# Phoreo.net
KiCad netlist of a schematic drawn in EAGLE
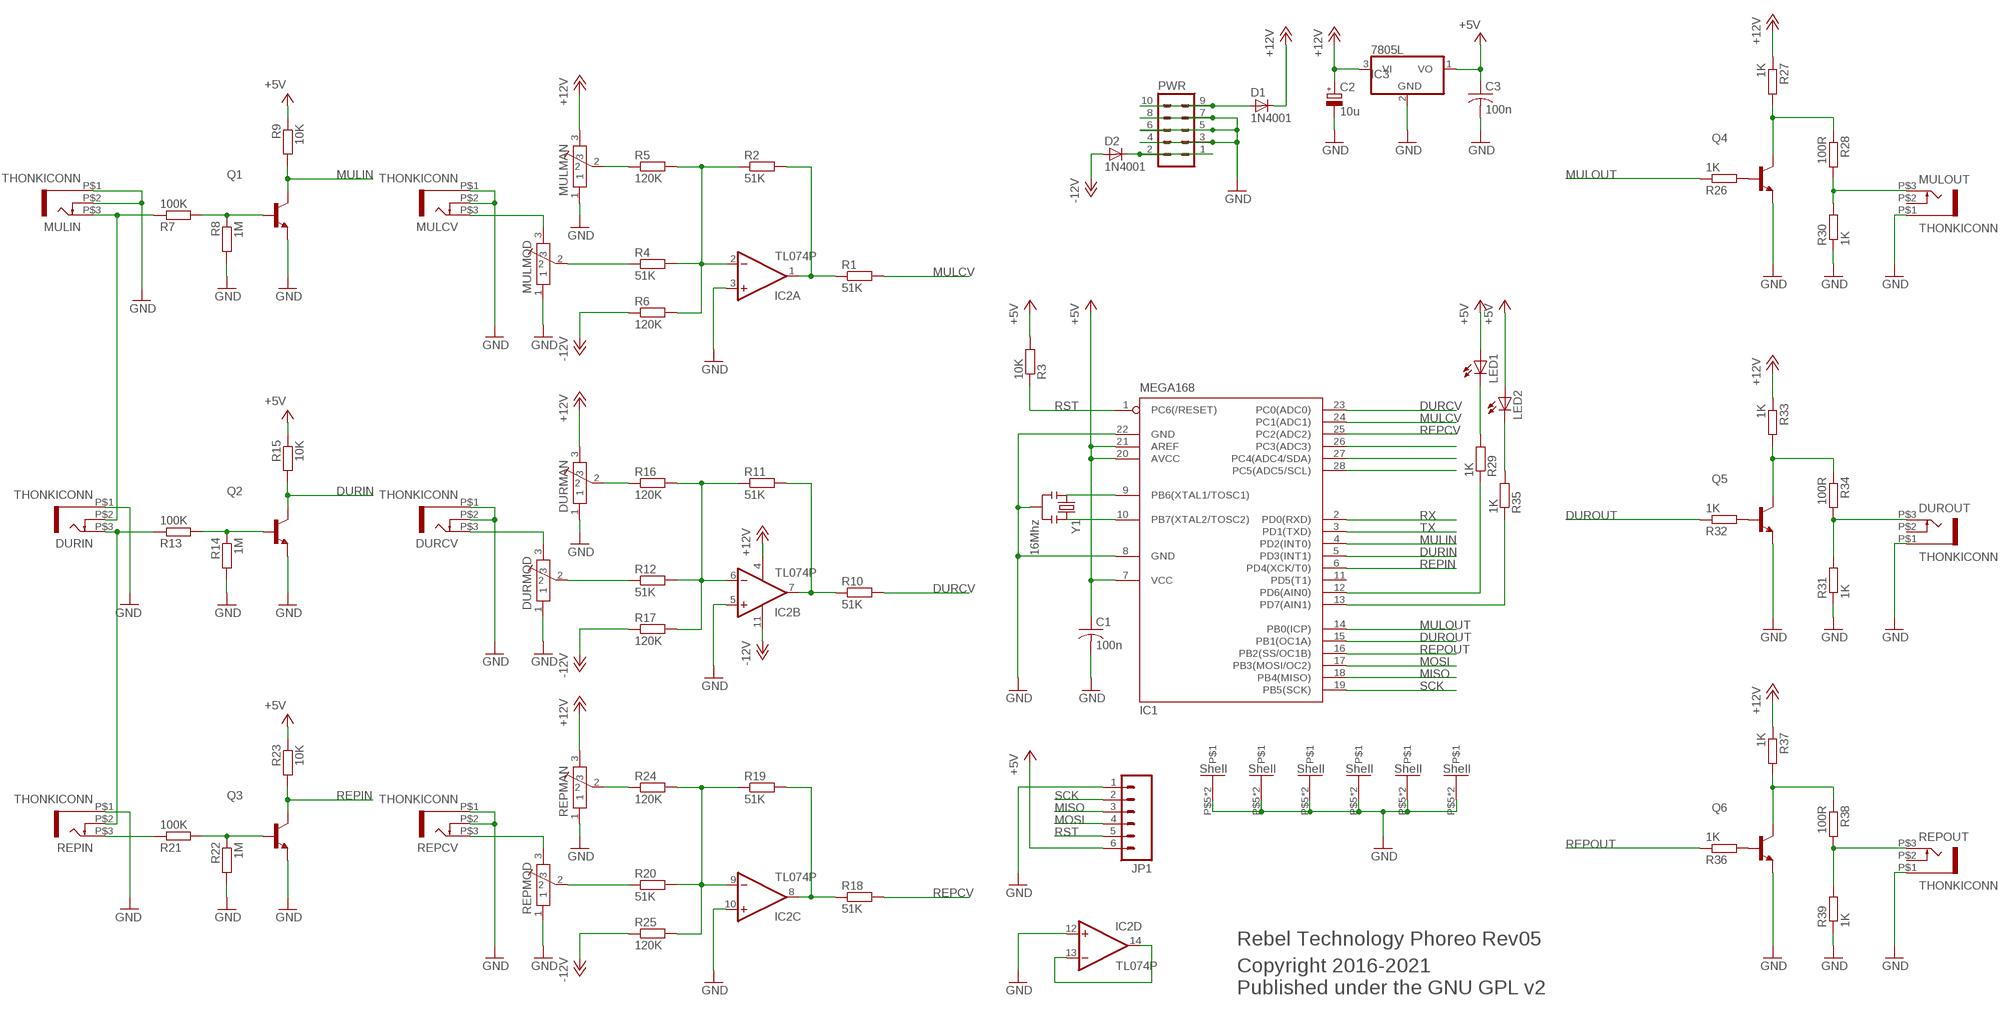
[diagram p0: schematic, sheet 1]

(export (version "E")
  (design (tool "Eeschema 10.0.6"))
  (components
    (comp (ref "C1")
      (value "100n")
      (footprint "eagle-import:C050-024X044")
      (libsource (lib "eagle-import") (part "C-US050-024X044"))
    )
    (comp (ref "C2")
      (value "10u")
      (footprint "eagle-import:E5-6")
      (libsource (lib "eagle-import") (part "CPOL-EUE5-6"))
    )
    (comp (ref "C3")
      (value "100n")
      (footprint "eagle-import:C050-024X044")
      (libsource (lib "eagle-import") (part "C-US050-024X044"))
    )
    (comp (ref "D1")
      (value "1N4001")
      (footprint "eagle-import:DIODE-1N4001")
      (libsource (lib "eagle-import") (part "DIODE1N4001"))
    )
    (comp (ref "D2")
      (value "1N4001")
      (footprint "eagle-import:DIODE-1N4001")
      (libsource (lib "eagle-import") (part "DIODE1N4001"))
    )
    (comp (ref "DURCV")
      (value "THONKICONN")
      (footprint "eagle-import:THONKICONN")
      (libsource (lib "eagle-import") (part "THONKICONN"))
    )
    (comp (ref "DURIN")
      (value "THONKICONN")
      (footprint "eagle-import:THONKICONN")
      (libsource (lib "eagle-import") (part "THONKICONN"))
    )
    (comp (ref "DURMAN")
      (value "POT-ALPS-RK09L1140")
      (footprint "eagle-import:POT-ALPS-RK09L1140")
      (libsource (lib "eagle-import") (part "POT-ALPS-RK09L1140"))
    )
    (comp (ref "DURMOD")
      (value "POT-ALPS-RK09L1140")
      (footprint "eagle-import:POT-ALPS-RK09L1140")
      (libsource (lib "eagle-import") (part "POT-ALPS-RK09L1140"))
    )
    (comp (ref "DUROUT")
      (value "THONKICONN")
      (footprint "eagle-import:THONKICONN")
      (libsource (lib "eagle-import") (part "THONKICONN"))
    )
    (comp (ref "IC1")
      (value "MEGA168")
      (footprint "eagle-import:DIL28-3")
      (libsource (lib "eagle-import") (part "MEGA8-P"))
    )
    (comp (ref "IC2")
      (value "TL074P")
      (footprint "eagle-import:DIL14")
      (libsource (lib "eagle-import") (part "TL074P"))
    )
    (comp (ref "IC3")
      (value "7805L")
      (footprint "eagle-import:TO92")
      (libsource (lib "eagle-import") (part "78L05"))
    )
    (comp (ref "JP1")
      (value "M06SIP")
      (footprint "eagle-import:1X06")
      (libsource (lib "eagle-import") (part "M06SIP"))
    )
    (comp (ref "LED1")
      (value "LED3MM")
      (footprint "eagle-import:LED3MM")
      (libsource (lib "eagle-import") (part "LED3MM"))
    )
    (comp (ref "LED2")
      (value "LED3MM")
      (footprint "eagle-import:LED3MM")
      (libsource (lib "eagle-import") (part "LED3MM"))
    )
    (comp (ref "MULCV")
      (value "THONKICONN")
      (footprint "eagle-import:THONKICONN")
      (libsource (lib "eagle-import") (part "THONKICONN"))
    )
    (comp (ref "MULIN")
      (value "THONKICONN")
      (footprint "eagle-import:THONKICONN")
      (libsource (lib "eagle-import") (part "THONKICONN"))
    )
    (comp (ref "MULMAN")
      (value "POT-ALPS-RK09L1140")
      (footprint "eagle-import:POT-ALPS-RK09L1140")
      (libsource (lib "eagle-import") (part "POT-ALPS-RK09L1140"))
    )
    (comp (ref "MULMOD")
      (value "POT-ALPS-RK09L1140")
      (footprint "eagle-import:POT-ALPS-RK09L1140")
      (libsource (lib "eagle-import") (part "POT-ALPS-RK09L1140"))
    )
    (comp (ref "MULOUT")
      (value "THONKICONN")
      (footprint "eagle-import:THONKICONN")
      (libsource (lib "eagle-import") (part "THONKICONN"))
    )
    (comp (ref "PWR")
      (value "MA05-2")
      (footprint "eagle-import:MA05-2")
      (libsource (lib "eagle-import") (part "MA05-2"))
    )
    (comp (ref "Q1")
      (value "2N3904-NPN-TO92-EBC")
      (footprint "eagle-import:TO92-EBC")
      (libsource (lib "eagle-import") (part "-NPN-TO92-EBC2N3904"))
    )
    (comp (ref "Q2")
      (value "2N3904-NPN-TO92-EBC")
      (footprint "eagle-import:TO92-EBC")
      (libsource (lib "eagle-import") (part "-NPN-TO92-EBC2N3904"))
    )
    (comp (ref "Q3")
      (value "2N3904-NPN-TO92-EBC")
      (footprint "eagle-import:TO92-EBC")
      (libsource (lib "eagle-import") (part "-NPN-TO92-EBC2N3904"))
    )
    (comp (ref "Q4")
      (value "2N3904-NPN-TO92-EBC")
      (footprint "eagle-import:TO92-EBC")
      (libsource (lib "eagle-import") (part "-NPN-TO92-EBC2N3904"))
    )
    (comp (ref "Q5")
      (value "2N3904-NPN-TO92-EBC")
      (footprint "eagle-import:TO92-EBC")
      (libsource (lib "eagle-import") (part "-NPN-TO92-EBC2N3904"))
    )
    (comp (ref "Q6")
      (value "2N3904-NPN-TO92-EBC")
      (footprint "eagle-import:TO92-EBC")
      (libsource (lib "eagle-import") (part "-NPN-TO92-EBC2N3904"))
    )
    (comp (ref "R1")
      (value "51K")
      (footprint "eagle-import:0204_7")
      (libsource (lib "eagle-import") (part "R-EU_0204/7"))
    )
    (comp (ref "R2")
      (value "51K")
      (footprint "eagle-import:0204_7")
      (libsource (lib "eagle-import") (part "R-EU_0204/7"))
    )
    (comp (ref "R3")
      (value "10K")
      (footprint "eagle-import:0204_7")
      (libsource (lib "eagle-import") (part "R-EU_0204/7"))
    )
    (comp (ref "R4")
      (value "51K")
      (footprint "eagle-import:0204_7")
      (libsource (lib "eagle-import") (part "R-EU_0204/7"))
    )
    (comp (ref "R5")
      (value "120K")
      (footprint "eagle-import:0204_7")
      (libsource (lib "eagle-import") (part "R-EU_0204/7"))
    )
    (comp (ref "R6")
      (value "120K")
      (footprint "eagle-import:0204_7")
      (libsource (lib "eagle-import") (part "R-EU_0204/7"))
    )
    (comp (ref "R7")
      (value "100K")
      (footprint "eagle-import:0204_7")
      (libsource (lib "eagle-import") (part "R-EU_0204/7"))
    )
    (comp (ref "R8")
      (value "1M")
      (footprint "eagle-import:0204_7")
      (libsource (lib "eagle-import") (part "R-EU_0204/7"))
    )
    (comp (ref "R9")
      (value "10K")
      (footprint "eagle-import:0204_7")
      (libsource (lib "eagle-import") (part "R-EU_0204/7"))
    )
    (comp (ref "R10")
      (value "51K")
      (footprint "eagle-import:0204_7")
      (libsource (lib "eagle-import") (part "R-EU_0204/7"))
    )
    (comp (ref "R11")
      (value "51K")
      (footprint "eagle-import:0204_7")
      (libsource (lib "eagle-import") (part "R-EU_0204/7"))
    )
    (comp (ref "R12")
      (value "51K")
      (footprint "eagle-import:0204_7")
      (libsource (lib "eagle-import") (part "R-EU_0204/7"))
    )
    (comp (ref "R13")
      (value "100K")
      (footprint "eagle-import:0204_7")
      (libsource (lib "eagle-import") (part "R-EU_0204/7"))
    )
    (comp (ref "R14")
      (value "1M")
      (footprint "eagle-import:0204_7")
      (libsource (lib "eagle-import") (part "R-EU_0204/7"))
    )
    (comp (ref "R15")
      (value "10K")
      (footprint "eagle-import:0204_7")
      (libsource (lib "eagle-import") (part "R-EU_0204/7"))
    )
    (comp (ref "R16")
      (value "120K")
      (footprint "eagle-import:0204_7")
      (libsource (lib "eagle-import") (part "R-EU_0204/7"))
    )
    (comp (ref "R17")
      (value "120K")
      (footprint "eagle-import:0204_7")
      (libsource (lib "eagle-import") (part "R-EU_0204/7"))
    )
    (comp (ref "R18")
      (value "51K")
      (footprint "eagle-import:0204_7")
      (libsource (lib "eagle-import") (part "R-EU_0204/7"))
    )
    (comp (ref "R19")
      (value "51K")
      (footprint "eagle-import:0204_7")
      (libsource (lib "eagle-import") (part "R-EU_0204/7"))
    )
    (comp (ref "R20")
      (value "51K")
      (footprint "eagle-import:0204_7")
      (libsource (lib "eagle-import") (part "R-EU_0204/7"))
    )
    (comp (ref "R21")
      (value "100K")
      (footprint "eagle-import:0204_7")
      (libsource (lib "eagle-import") (part "R-EU_0204/7"))
    )
    (comp (ref "R22")
      (value "1M")
      (footprint "eagle-import:0204_7")
      (libsource (lib "eagle-import") (part "R-EU_0204/7"))
    )
    (comp (ref "R23")
      (value "10K")
      (footprint "eagle-import:0204_7")
      (libsource (lib "eagle-import") (part "R-EU_0204/7"))
    )
    (comp (ref "R24")
      (value "120K")
      (footprint "eagle-import:0204_7")
      (libsource (lib "eagle-import") (part "R-EU_0204/7"))
    )
    (comp (ref "R25")
      (value "120K")
      (footprint "eagle-import:0204_7")
      (libsource (lib "eagle-import") (part "R-EU_0204/7"))
    )
    (comp (ref "R26")
      (value "1K")
      (footprint "eagle-import:0204_7")
      (libsource (lib "eagle-import") (part "R-EU_0204/7"))
    )
    (comp (ref "R27")
      (value "1K")
      (footprint "eagle-import:0204_7")
      (libsource (lib "eagle-import") (part "R-EU_0204/7"))
    )
    (comp (ref "R28")
      (value "100R")
      (footprint "eagle-import:0204_7")
      (libsource (lib "eagle-import") (part "R-EU_0204/7"))
    )
    (comp (ref "R29")
      (value "1K")
      (footprint "eagle-import:0204_7")
      (libsource (lib "eagle-import") (part "R-EU_0204/7"))
    )
    (comp (ref "R30")
      (value "1K")
      (footprint "eagle-import:0204_7")
      (libsource (lib "eagle-import") (part "R-EU_0204/7"))
    )
    (comp (ref "R31")
      (value "1K")
      (footprint "eagle-import:0204_7")
      (libsource (lib "eagle-import") (part "R-EU_0204/7"))
    )
    (comp (ref "R32")
      (value "1K")
      (footprint "eagle-import:0204_7")
      (libsource (lib "eagle-import") (part "R-EU_0204/7"))
    )
    (comp (ref "R33")
      (value "1K")
      (footprint "eagle-import:0204_7")
      (libsource (lib "eagle-import") (part "R-EU_0204/7"))
    )
    (comp (ref "R34")
      (value "100R")
      (footprint "eagle-import:0204_7")
      (libsource (lib "eagle-import") (part "R-EU_0204/7"))
    )
    (comp (ref "R35")
      (value "1K")
      (footprint "eagle-import:0204_7")
      (libsource (lib "eagle-import") (part "R-EU_0204/7"))
    )
    (comp (ref "R36")
      (value "1K")
      (footprint "eagle-import:0204_7")
      (libsource (lib "eagle-import") (part "R-EU_0204/7"))
    )
    (comp (ref "R37")
      (value "1K")
      (footprint "eagle-import:0204_7")
      (libsource (lib "eagle-import") (part "R-EU_0204/7"))
    )
    (comp (ref "R38")
      (value "100R")
      (footprint "eagle-import:0204_7")
      (libsource (lib "eagle-import") (part "R-EU_0204/7"))
    )
    (comp (ref "R39")
      (value "1K")
      (footprint "eagle-import:0204_7")
      (libsource (lib "eagle-import") (part "R-EU_0204/7"))
    )
    (comp (ref "REPCV")
      (value "THONKICONN")
      (footprint "eagle-import:THONKICONN")
      (libsource (lib "eagle-import") (part "THONKICONN"))
    )
    (comp (ref "REPIN")
      (value "THONKICONN")
      (footprint "eagle-import:THONKICONN")
      (libsource (lib "eagle-import") (part "THONKICONN"))
    )
    (comp (ref "REPMAN")
      (value "POT-ALPS-RK09L1140")
      (footprint "eagle-import:POT-ALPS-RK09L1140")
      (libsource (lib "eagle-import") (part "POT-ALPS-RK09L1140"))
    )
    (comp (ref "REPMOD")
      (value "POT-ALPS-RK09L1140")
      (footprint "eagle-import:POT-ALPS-RK09L1140")
      (libsource (lib "eagle-import") (part "POT-ALPS-RK09L1140"))
    )
    (comp (ref "REPOUT")
      (value "THONKICONN")
      (footprint "eagle-import:THONKICONN")
      (libsource (lib "eagle-import") (part "THONKICONN"))
    )
    (comp (ref "Y1")
      (value "16Mhz")
      (footprint "eagle-import:RESONATOR-PTH")
      (libsource (lib "eagle-import") (part "RESONATORPTH"))
    )
  )
  (nets
    (net (code "1") (name "+5V") (class "Default")
      (node (ref "C1") (pin "1") (pinfunction "1_1") (pintype "passive"))
      (node (ref "C3") (pin "1") (pinfunction "1_1") (pintype "passive"))
      (node (ref "IC1") (pin "20") (pinfunction "AVCC_20") (pintype "power_in"))
      (node (ref "IC1") (pin "21") (pinfunction "AREF_21") (pintype "passive"))
      (node (ref "IC1") (pin "7") (pinfunction "VCC_7") (pintype "power_in"))
      (node (ref "IC3") (pin "1") (pinfunction "VO_1") (pintype "passive"))
      (node (ref "JP1") (pin "6") (pinfunction "6_6") (pintype "passive"))
      (node (ref "LED1") (pin "A") (pinfunction "A_A") (pintype "passive"))
      (node (ref "LED2") (pin "A") (pinfunction "A_A") (pintype "passive"))
      (node (ref "R15") (pin "1") (pinfunction "1_1") (pintype "passive"))
      (node (ref "R23") (pin "1") (pinfunction "1_1") (pintype "passive"))
      (node (ref "R3") (pin "2") (pinfunction "2_2") (pintype "passive"))
      (node (ref "R9") (pin "1") (pinfunction "1_1") (pintype "passive"))
    )
    (net (code "2") (name "+12V") (class "Default")
      (node (ref "C2") (pin "+") (pinfunction "+_+") (pintype "passive"))
      (node (ref "D1") (pin "C") (pinfunction "C_C") (pintype "passive"))
      (node (ref "DURMAN") (pin "3") (pinfunction "3_3") (pintype "bidirectional"))
      (node (ref "IC2") (pin "4") (pinfunction "V+_4") (pintype "power_in"))
      (node (ref "IC3") (pin "3") (pinfunction "VI_3") (pintype "input"))
      (node (ref "MULMAN") (pin "3") (pinfunction "3_3") (pintype "bidirectional"))
      (node (ref "R27") (pin "1") (pinfunction "1_1") (pintype "passive"))
      (node (ref "R33") (pin "1") (pinfunction "1_1") (pintype "passive"))
      (node (ref "R37") (pin "1") (pinfunction "1_1") (pintype "passive"))
      (node (ref "REPMAN") (pin "3") (pinfunction "3_3") (pintype "bidirectional"))
    )
    (net (code "3") (name "-12V") (class "Default")
      (node (ref "D2") (pin "A") (pinfunction "A_A") (pintype "passive"))
      (node (ref "IC2") (pin "11") (pinfunction "V-_11") (pintype "power_in"))
      (node (ref "R17") (pin "1") (pinfunction "1_1") (pintype "passive"))
      (node (ref "R25") (pin "1") (pinfunction "1_1") (pintype "passive"))
      (node (ref "R6") (pin "1") (pinfunction "1_1") (pintype "passive"))
    )
    (net (code "4") (name "/DURCV") (class "Default")
      (node (ref "IC1") (pin "23") (pinfunction "PC0(ADC0)_23") (pintype "bidirectional"))
      (node (ref "R10") (pin "2") (pinfunction "2_2") (pintype "passive"))
    )
    (net (code "5") (name "/DURIN") (class "Default")
      (node (ref "IC1") (pin "5") (pinfunction "PD3(INT1)_5") (pintype "bidirectional"))
      (node (ref "Q2") (pin "C") (pinfunction "C_C") (pintype "passive"))
      (node (ref "R15") (pin "2") (pinfunction "2_2") (pintype "passive"))
    )
    (net (code "6") (name "/DUROUT") (class "Default")
      (node (ref "IC1") (pin "15") (pinfunction "PB1(OC1A)_15") (pintype "bidirectional"))
      (node (ref "R32") (pin "1") (pinfunction "1_1") (pintype "passive"))
    )
    (net (code "7") (name "/MISO") (class "Default")
      (node (ref "IC1") (pin "18") (pinfunction "PB4(MISO)_18") (pintype "bidirectional"))
      (node (ref "JP1") (pin "3") (pinfunction "3_3") (pintype "passive"))
    )
    (net (code "8") (name "/MOSI") (class "Default")
      (node (ref "IC1") (pin "17") (pinfunction "PB3(MOSI/OC2)_17") (pintype "bidirectional"))
      (node (ref "JP1") (pin "4") (pinfunction "4_4") (pintype "passive"))
    )
    (net (code "9") (name "/MULCV") (class "Default")
      (node (ref "IC1") (pin "24") (pinfunction "PC1(ADC1)_24") (pintype "bidirectional"))
      (node (ref "R1") (pin "2") (pinfunction "2_2") (pintype "passive"))
    )
    (net (code "10") (name "/MULIN") (class "Default")
      (node (ref "IC1") (pin "4") (pinfunction "PD2(INT0)_4") (pintype "bidirectional"))
      (node (ref "Q1") (pin "C") (pinfunction "C_C") (pintype "passive"))
      (node (ref "R9") (pin "2") (pinfunction "2_2") (pintype "passive"))
    )
    (net (code "11") (name "/MULOUT") (class "Default")
      (node (ref "IC1") (pin "14") (pinfunction "PB0(ICP)_14") (pintype "bidirectional"))
      (node (ref "R26") (pin "1") (pinfunction "1_1") (pintype "passive"))
    )
    (net (code "12") (name "/REPCV") (class "Default")
      (node (ref "IC1") (pin "25") (pinfunction "PC2(ADC2)_25") (pintype "bidirectional"))
      (node (ref "R18") (pin "2") (pinfunction "2_2") (pintype "passive"))
    )
    (net (code "13") (name "/REPIN") (class "Default")
      (node (ref "IC1") (pin "6") (pinfunction "PD4(XCK/T0)_6") (pintype "bidirectional"))
      (node (ref "Q3") (pin "C") (pinfunction "C_C") (pintype "passive"))
      (node (ref "R23") (pin "2") (pinfunction "2_2") (pintype "passive"))
    )
    (net (code "14") (name "/REPOUT") (class "Default")
      (node (ref "IC1") (pin "16") (pinfunction "PB2(SS/OC1B)_16") (pintype "bidirectional"))
      (node (ref "R36") (pin "1") (pinfunction "1_1") (pintype "passive"))
    )
    (net (code "15") (name "/RST") (class "Default")
      (node (ref "IC1") (pin "1") (pinfunction "PC6(/RESET)_1") (pintype "bidirectional"))
      (node (ref "JP1") (pin "5") (pinfunction "5_5") (pintype "passive"))
      (node (ref "R3") (pin "1") (pinfunction "1_1") (pintype "passive"))
    )
    (net (code "16") (name "/RX") (class "Default")
      (node (ref "IC1") (pin "2") (pinfunction "PD0(RXD)_2") (pintype "bidirectional"))
    )
    (net (code "17") (name "/SCK") (class "Default")
      (node (ref "IC1") (pin "19") (pinfunction "PB5(SCK)_19") (pintype "bidirectional"))
      (node (ref "JP1") (pin "2") (pinfunction "2_2") (pintype "passive"))
    )
    (net (code "18") (name "/TX") (class "Default")
      (node (ref "IC1") (pin "3") (pinfunction "PD1(TXD)_3") (pintype "bidirectional"))
    )
    (net (code "19") (name "GND") (class "Default")
      (node (ref "C1") (pin "2") (pinfunction "2_2") (pintype "passive"))
      (node (ref "C2") (pin "-") (pinfunction "-_-") (pintype "passive"))
      (node (ref "C3") (pin "2") (pinfunction "2_2") (pintype "passive"))
      (node (ref "DURCV") (pin "P$1") (pinfunction "5_P$1") (pintype "passive"))
      (node (ref "DURCV") (pin "P$2") (pinfunction "4_P$2") (pintype "passive"))
      (node (ref "DURIN") (pin "P$1") (pinfunction "5_P$1") (pintype "passive"))
      (node (ref "DURMAN") (pin "1") (pinfunction "1_1") (pintype "bidirectional"))
      (node (ref "DURMAN") (pin "P$5") (pinfunction "P$1_P$5") (pintype "bidirectional"))
      (node (ref "DURMAN") (pin "P$6") (pinfunction "P$1_P$6") (pintype "bidirectional"))
      (node (ref "DURMOD") (pin "1") (pinfunction "1_1") (pintype "bidirectional"))
      (node (ref "DURMOD") (pin "P$5") (pinfunction "P$1_P$5") (pintype "bidirectional"))
      (node (ref "DURMOD") (pin "P$6") (pinfunction "P$1_P$6") (pintype "bidirectional"))
      (node (ref "DUROUT") (pin "P$1") (pinfunction "5_P$1") (pintype "passive"))
      (node (ref "IC1") (pin "22") (pinfunction "GND_22") (pintype "power_in"))
      (node (ref "IC1") (pin "8") (pinfunction "GND_8") (pintype "power_in"))
      (node (ref "IC2") (pin "10") (pinfunction "+IN_10") (pintype "input"))
      (node (ref "IC2") (pin "12") (pinfunction "+IN_12") (pintype "input"))
      (node (ref "IC2") (pin "3") (pinfunction "+IN_3") (pintype "input"))
      (node (ref "IC2") (pin "5") (pinfunction "+IN_5") (pintype "input"))
      (node (ref "IC3") (pin "2") (pinfunction "GND_2") (pintype "passive"))
      (node (ref "JP1") (pin "1") (pinfunction "1_1") (pintype "passive"))
      (node (ref "MULCV") (pin "P$1") (pinfunction "5_P$1") (pintype "passive"))
      (node (ref "MULCV") (pin "P$2") (pinfunction "4_P$2") (pintype "passive"))
      (node (ref "MULIN") (pin "P$1") (pinfunction "5_P$1") (pintype "passive"))
      (node (ref "MULIN") (pin "P$2") (pinfunction "4_P$2") (pintype "passive"))
      (node (ref "MULMAN") (pin "1") (pinfunction "1_1") (pintype "bidirectional"))
      (node (ref "MULMAN") (pin "P$5") (pinfunction "P$1_P$5") (pintype "bidirectional"))
      (node (ref "MULMAN") (pin "P$6") (pinfunction "P$1_P$6") (pintype "bidirectional"))
      (node (ref "MULMOD") (pin "1") (pinfunction "1_1") (pintype "bidirectional"))
      (node (ref "MULMOD") (pin "P$5") (pinfunction "P$1_P$5") (pintype "bidirectional"))
      (node (ref "MULMOD") (pin "P$6") (pinfunction "P$1_P$6") (pintype "bidirectional"))
      (node (ref "MULOUT") (pin "P$1") (pinfunction "5_P$1") (pintype "passive"))
      (node (ref "PWR") (pin "3") (pinfunction "3_3") (pintype "passive"))
      (node (ref "PWR") (pin "4") (pinfunction "4_4") (pintype "passive"))
      (node (ref "PWR") (pin "5") (pinfunction "5_5") (pintype "passive"))
      (node (ref "PWR") (pin "6") (pinfunction "6_6") (pintype "passive"))
      (node (ref "PWR") (pin "7") (pinfunction "7_7") (pintype "passive"))
      (node (ref "PWR") (pin "8") (pinfunction "8_8") (pintype "passive"))
      (node (ref "Q1") (pin "E") (pinfunction "E_E") (pintype "passive"))
      (node (ref "Q2") (pin "E") (pinfunction "E_E") (pintype "passive"))
      (node (ref "Q3") (pin "E") (pinfunction "E_E") (pintype "passive"))
      (node (ref "Q4") (pin "E") (pinfunction "E_E") (pintype "passive"))
      (node (ref "Q5") (pin "E") (pinfunction "E_E") (pintype "passive"))
      (node (ref "Q6") (pin "E") (pinfunction "E_E") (pintype "passive"))
      (node (ref "R14") (pin "2") (pinfunction "2_2") (pintype "passive"))
      (node (ref "R22") (pin "2") (pinfunction "2_2") (pintype "passive"))
      (node (ref "R30") (pin "1") (pinfunction "1_1") (pintype "passive"))
      (node (ref "R31") (pin "1") (pinfunction "1_1") (pintype "passive"))
      (node (ref "R39") (pin "1") (pinfunction "1_1") (pintype "passive"))
      (node (ref "R8") (pin "2") (pinfunction "2_2") (pintype "passive"))
      (node (ref "REPCV") (pin "P$1") (pinfunction "5_P$1") (pintype "passive"))
      (node (ref "REPCV") (pin "P$2") (pinfunction "4_P$2") (pintype "passive"))
      (node (ref "REPIN") (pin "P$1") (pinfunction "5_P$1") (pintype "passive"))
      (node (ref "REPMAN") (pin "1") (pinfunction "1_1") (pintype "bidirectional"))
      (node (ref "REPMAN") (pin "P$5") (pinfunction "P$1_P$5") (pintype "bidirectional"))
      (node (ref "REPMAN") (pin "P$6") (pinfunction "P$1_P$6") (pintype "bidirectional"))
      (node (ref "REPMOD") (pin "1") (pinfunction "1_1") (pintype "bidirectional"))
      (node (ref "REPMOD") (pin "P$5") (pinfunction "P$1_P$5") (pintype "bidirectional"))
      (node (ref "REPMOD") (pin "P$6") (pinfunction "P$1_P$6") (pintype "bidirectional"))
      (node (ref "REPOUT") (pin "P$1") (pinfunction "5_P$1") (pintype "passive"))
      (node (ref "Y1") (pin "2") (pinfunction "2_2") (pintype "passive"))
    )
    (net (code "20") (name "Net-(D1-PadA)") (class "Default")
      (node (ref "D1") (pin "A") (pinfunction "A_A") (pintype "passive"))
      (node (ref "PWR") (pin "10") (pinfunction "10_10") (pintype "passive"))
      (node (ref "PWR") (pin "9") (pinfunction "9_9") (pintype "passive"))
    )
    (net (code "21") (name "Net-(D2-PadC)") (class "Default")
      (node (ref "D2") (pin "C") (pinfunction "C_C") (pintype "passive"))
      (node (ref "PWR") (pin "1") (pinfunction "1_1") (pintype "passive"))
      (node (ref "PWR") (pin "2") (pinfunction "2_2") (pintype "passive"))
    )
    (net (code "22") (name "Net-(DURCV-3)") (class "Default")
      (node (ref "DURCV") (pin "P$3") (pinfunction "3_P$3") (pintype "passive"))
      (node (ref "DURMOD") (pin "3") (pinfunction "3_3") (pintype "bidirectional"))
    )
    (net (code "23") (name "Net-(DURIN-3)") (class "Default")
      (node (ref "DURIN") (pin "P$3") (pinfunction "3_P$3") (pintype "passive"))
      (node (ref "R13") (pin "1") (pinfunction "1_1") (pintype "passive"))
      (node (ref "REPIN") (pin "P$2") (pinfunction "4_P$2") (pintype "passive"))
    )
    (net (code "24") (name "Net-(DURIN-4)") (class "Default")
      (node (ref "DURIN") (pin "P$2") (pinfunction "4_P$2") (pintype "passive"))
      (node (ref "MULIN") (pin "P$3") (pinfunction "3_P$3") (pintype "passive"))
      (node (ref "R7") (pin "1") (pinfunction "1_1") (pintype "passive"))
    )
    (net (code "25") (name "Net-(DURMAN-Pad2)") (class "Default")
      (node (ref "DURMAN") (pin "2") (pinfunction "2_2") (pintype "bidirectional"))
      (node (ref "R16") (pin "1") (pinfunction "1_1") (pintype "passive"))
    )
    (net (code "26") (name "Net-(DURMOD-Pad2)") (class "Default")
      (node (ref "DURMOD") (pin "2") (pinfunction "2_2") (pintype "bidirectional"))
      (node (ref "R12") (pin "1") (pinfunction "1_1") (pintype "passive"))
    )
    (net (code "27") (name "Net-(DUROUT-3)") (class "Default")
      (node (ref "DUROUT") (pin "P$3") (pinfunction "3_P$3") (pintype "passive"))
      (node (ref "R31") (pin "2") (pinfunction "2_2") (pintype "passive"))
      (node (ref "R34") (pin "2") (pinfunction "2_2") (pintype "passive"))
    )
    (net (code "28") (name "Net-(IC1-PB6(XTAL1{slash}TOSC1))") (class "Default")
      (node (ref "IC1") (pin "9") (pinfunction "PB6(XTAL1/TOSC1)_9") (pintype "bidirectional"))
      (node (ref "Y1") (pin "1") (pinfunction "1_1") (pintype "passive"))
    )
    (net (code "29") (name "Net-(IC1-PB7(XTAL2{slash}TOSC2))") (class "Default")
      (node (ref "IC1") (pin "10") (pinfunction "PB7(XTAL2/TOSC2)_10") (pintype "bidirectional"))
      (node (ref "Y1") (pin "3") (pinfunction "3_3") (pintype "passive"))
    )
    (net (code "30") (name "Net-(IC1-PD6(AIN0))") (class "Default")
      (node (ref "IC1") (pin "12") (pinfunction "PD6(AIN0)_12") (pintype "bidirectional"))
      (node (ref "R29") (pin "1") (pinfunction "1_1") (pintype "passive"))
    )
    (net (code "31") (name "Net-(IC1-PD7(AIN1))") (class "Default")
      (node (ref "IC1") (pin "13") (pinfunction "PD7(AIN1)_13") (pintype "bidirectional"))
      (node (ref "R35") (pin "1") (pinfunction "1_1") (pintype "passive"))
    )
    (net (code "32") (name "Net-(IC2A--IN)") (class "Default")
      (node (ref "IC2") (pin "2") (pinfunction "-IN_2") (pintype "input"))
      (node (ref "R2") (pin "1") (pinfunction "1_1") (pintype "passive"))
      (node (ref "R4") (pin "2") (pinfunction "2_2") (pintype "passive"))
      (node (ref "R5") (pin "2") (pinfunction "2_2") (pintype "passive"))
      (node (ref "R6") (pin "2") (pinfunction "2_2") (pintype "passive"))
    )
    (net (code "33") (name "Net-(IC2A-OUT)") (class "Default")
      (node (ref "IC2") (pin "1") (pinfunction "OUT_1") (pintype "output"))
      (node (ref "R1") (pin "1") (pinfunction "1_1") (pintype "passive"))
      (node (ref "R2") (pin "2") (pinfunction "2_2") (pintype "passive"))
    )
    (net (code "34") (name "Net-(IC2B--IN)") (class "Default")
      (node (ref "IC2") (pin "6") (pinfunction "-IN_6") (pintype "input"))
      (node (ref "R11") (pin "1") (pinfunction "1_1") (pintype "passive"))
      (node (ref "R12") (pin "2") (pinfunction "2_2") (pintype "passive"))
      (node (ref "R16") (pin "2") (pinfunction "2_2") (pintype "passive"))
      (node (ref "R17") (pin "2") (pinfunction "2_2") (pintype "passive"))
    )
    (net (code "35") (name "Net-(IC2B-OUT)") (class "Default")
      (node (ref "IC2") (pin "7") (pinfunction "OUT_7") (pintype "output"))
      (node (ref "R10") (pin "1") (pinfunction "1_1") (pintype "passive"))
      (node (ref "R11") (pin "2") (pinfunction "2_2") (pintype "passive"))
    )
    (net (code "36") (name "Net-(IC2C--IN)") (class "Default")
      (node (ref "IC2") (pin "9") (pinfunction "-IN_9") (pintype "input"))
      (node (ref "R19") (pin "1") (pinfunction "1_1") (pintype "passive"))
      (node (ref "R20") (pin "2") (pinfunction "2_2") (pintype "passive"))
      (node (ref "R24") (pin "2") (pinfunction "2_2") (pintype "passive"))
      (node (ref "R25") (pin "2") (pinfunction "2_2") (pintype "passive"))
    )
    (net (code "37") (name "Net-(IC2C-OUT)") (class "Default")
      (node (ref "IC2") (pin "8") (pinfunction "OUT_8") (pintype "output"))
      (node (ref "R18") (pin "1") (pinfunction "1_1") (pintype "passive"))
      (node (ref "R19") (pin "2") (pinfunction "2_2") (pintype "passive"))
    )
    (net (code "38") (name "Net-(IC2D--IN)") (class "Default")
      (node (ref "IC2") (pin "13") (pinfunction "-IN_13") (pintype "input"))
      (node (ref "IC2") (pin "14") (pinfunction "OUT_14") (pintype "output"))
    )
    (net (code "39") (name "Net-(LED1-C)") (class "Default")
      (node (ref "LED1") (pin "K") (pinfunction "C_K") (pintype "passive"))
      (node (ref "R29") (pin "2") (pinfunction "2_2") (pintype "passive"))
    )
    (net (code "40") (name "Net-(LED2-C)") (class "Default")
      (node (ref "LED2") (pin "K") (pinfunction "C_K") (pintype "passive"))
      (node (ref "R35") (pin "2") (pinfunction "2_2") (pintype "passive"))
    )
    (net (code "41") (name "Net-(MULCV-3)") (class "Default")
      (node (ref "MULCV") (pin "P$3") (pinfunction "3_P$3") (pintype "passive"))
      (node (ref "MULMOD") (pin "3") (pinfunction "3_3") (pintype "bidirectional"))
    )
    (net (code "42") (name "Net-(MULMAN-Pad2)") (class "Default")
      (node (ref "MULMAN") (pin "2") (pinfunction "2_2") (pintype "bidirectional"))
      (node (ref "R5") (pin "1") (pinfunction "1_1") (pintype "passive"))
    )
    (net (code "43") (name "Net-(MULMOD-Pad2)") (class "Default")
      (node (ref "MULMOD") (pin "2") (pinfunction "2_2") (pintype "bidirectional"))
      (node (ref "R4") (pin "1") (pinfunction "1_1") (pintype "passive"))
    )
    (net (code "44") (name "Net-(MULOUT-3)") (class "Default")
      (node (ref "MULOUT") (pin "P$3") (pinfunction "3_P$3") (pintype "passive"))
      (node (ref "R28") (pin "2") (pinfunction "2_2") (pintype "passive"))
      (node (ref "R30") (pin "2") (pinfunction "2_2") (pintype "passive"))
    )
    (net (code "45") (name "Net-(Q1-PadB)") (class "Default")
      (node (ref "Q1") (pin "B") (pinfunction "B_B") (pintype "passive"))
      (node (ref "R7") (pin "2") (pinfunction "2_2") (pintype "passive"))
      (node (ref "R8") (pin "1") (pinfunction "1_1") (pintype "passive"))
    )
    (net (code "46") (name "Net-(Q2-PadB)") (class "Default")
      (node (ref "Q2") (pin "B") (pinfunction "B_B") (pintype "passive"))
      (node (ref "R13") (pin "2") (pinfunction "2_2") (pintype "passive"))
      (node (ref "R14") (pin "1") (pinfunction "1_1") (pintype "passive"))
    )
    (net (code "47") (name "Net-(Q3-PadB)") (class "Default")
      (node (ref "Q3") (pin "B") (pinfunction "B_B") (pintype "passive"))
      (node (ref "R21") (pin "2") (pinfunction "2_2") (pintype "passive"))
      (node (ref "R22") (pin "1") (pinfunction "1_1") (pintype "passive"))
    )
    (net (code "48") (name "Net-(Q4-PadB)") (class "Default")
      (node (ref "Q4") (pin "B") (pinfunction "B_B") (pintype "passive"))
      (node (ref "R26") (pin "2") (pinfunction "2_2") (pintype "passive"))
    )
    (net (code "49") (name "Net-(Q4-PadC)") (class "Default")
      (node (ref "Q4") (pin "C") (pinfunction "C_C") (pintype "passive"))
      (node (ref "R27") (pin "2") (pinfunction "2_2") (pintype "passive"))
      (node (ref "R28") (pin "1") (pinfunction "1_1") (pintype "passive"))
    )
    (net (code "50") (name "Net-(Q5-PadB)") (class "Default")
      (node (ref "Q5") (pin "B") (pinfunction "B_B") (pintype "passive"))
      (node (ref "R32") (pin "2") (pinfunction "2_2") (pintype "passive"))
    )
    (net (code "51") (name "Net-(Q5-PadC)") (class "Default")
      (node (ref "Q5") (pin "C") (pinfunction "C_C") (pintype "passive"))
      (node (ref "R33") (pin "2") (pinfunction "2_2") (pintype "passive"))
      (node (ref "R34") (pin "1") (pinfunction "1_1") (pintype "passive"))
    )
    (net (code "52") (name "Net-(Q6-PadB)") (class "Default")
      (node (ref "Q6") (pin "B") (pinfunction "B_B") (pintype "passive"))
      (node (ref "R36") (pin "2") (pinfunction "2_2") (pintype "passive"))
    )
    (net (code "53") (name "Net-(Q6-PadC)") (class "Default")
      (node (ref "Q6") (pin "C") (pinfunction "C_C") (pintype "passive"))
      (node (ref "R37") (pin "2") (pinfunction "2_2") (pintype "passive"))
      (node (ref "R38") (pin "1") (pinfunction "1_1") (pintype "passive"))
    )
    (net (code "54") (name "Net-(R20-Pad1)") (class "Default")
      (node (ref "R20") (pin "1") (pinfunction "1_1") (pintype "passive"))
      (node (ref "REPMOD") (pin "2") (pinfunction "2_2") (pintype "bidirectional"))
    )
    (net (code "55") (name "Net-(R24-Pad1)") (class "Default")
      (node (ref "R24") (pin "1") (pinfunction "1_1") (pintype "passive"))
      (node (ref "REPMAN") (pin "2") (pinfunction "2_2") (pintype "bidirectional"))
    )
    (net (code "56") (name "Net-(REPCV-3)") (class "Default")
      (node (ref "REPCV") (pin "P$3") (pinfunction "3_P$3") (pintype "passive"))
      (node (ref "REPMOD") (pin "3") (pinfunction "3_3") (pintype "bidirectional"))
    )
    (net (code "57") (name "Net-(REPIN-3)") (class "Default")
      (node (ref "R21") (pin "1") (pinfunction "1_1") (pintype "passive"))
      (node (ref "REPIN") (pin "P$3") (pinfunction "3_P$3") (pintype "passive"))
    )
    (net (code "58") (name "Net-(REPOUT-3)") (class "Default")
      (node (ref "R38") (pin "2") (pinfunction "2_2") (pintype "passive"))
      (node (ref "R39") (pin "2") (pinfunction "2_2") (pintype "passive"))
      (node (ref "REPOUT") (pin "P$3") (pinfunction "3_P$3") (pintype "passive"))
    )
    (net (code "59") (name "unconnected-(DUROUT-4-PadP$2)") (class "Default")
      (node (ref "DUROUT") (pin "P$2") (pinfunction "4_P$2") (pintype "passive"))
    )
    (net (code "60") (name "unconnected-(IC1-PC3(ADC3)-Pad26)") (class "Default")
      (node (ref "IC1") (pin "26") (pinfunction "PC3(ADC3)_26") (pintype "bidirectional"))
    )
    (net (code "61") (name "unconnected-(IC1-PC4(ADC4{slash}SDA)-Pad27)") (class "Default")
      (node (ref "IC1") (pin "27") (pinfunction "PC4(ADC4/SDA)_27") (pintype "bidirectional"))
    )
    (net (code "62") (name "unconnected-(IC1-PC5(ADC5{slash}SCL)-Pad28)") (class "Default")
      (node (ref "IC1") (pin "28") (pinfunction "PC5(ADC5/SCL)_28") (pintype "bidirectional"))
    )
    (net (code "63") (name "unconnected-(IC1-PD5(T1)-Pad11)") (class "Default")
      (node (ref "IC1") (pin "11") (pinfunction "PD5(T1)_11") (pintype "bidirectional"))
    )
    (net (code "64") (name "unconnected-(MULOUT-4-PadP$2)") (class "Default")
      (node (ref "MULOUT") (pin "P$2") (pinfunction "4_P$2") (pintype "passive"))
    )
    (net (code "65") (name "unconnected-(REPOUT-4-PadP$2)") (class "Default")
      (node (ref "REPOUT") (pin "P$2") (pinfunction "4_P$2") (pintype "passive"))
    )
  )
)
